# oresat-plusz-end-card.net
KiCad netlist of a schematic drawn in EAGLE
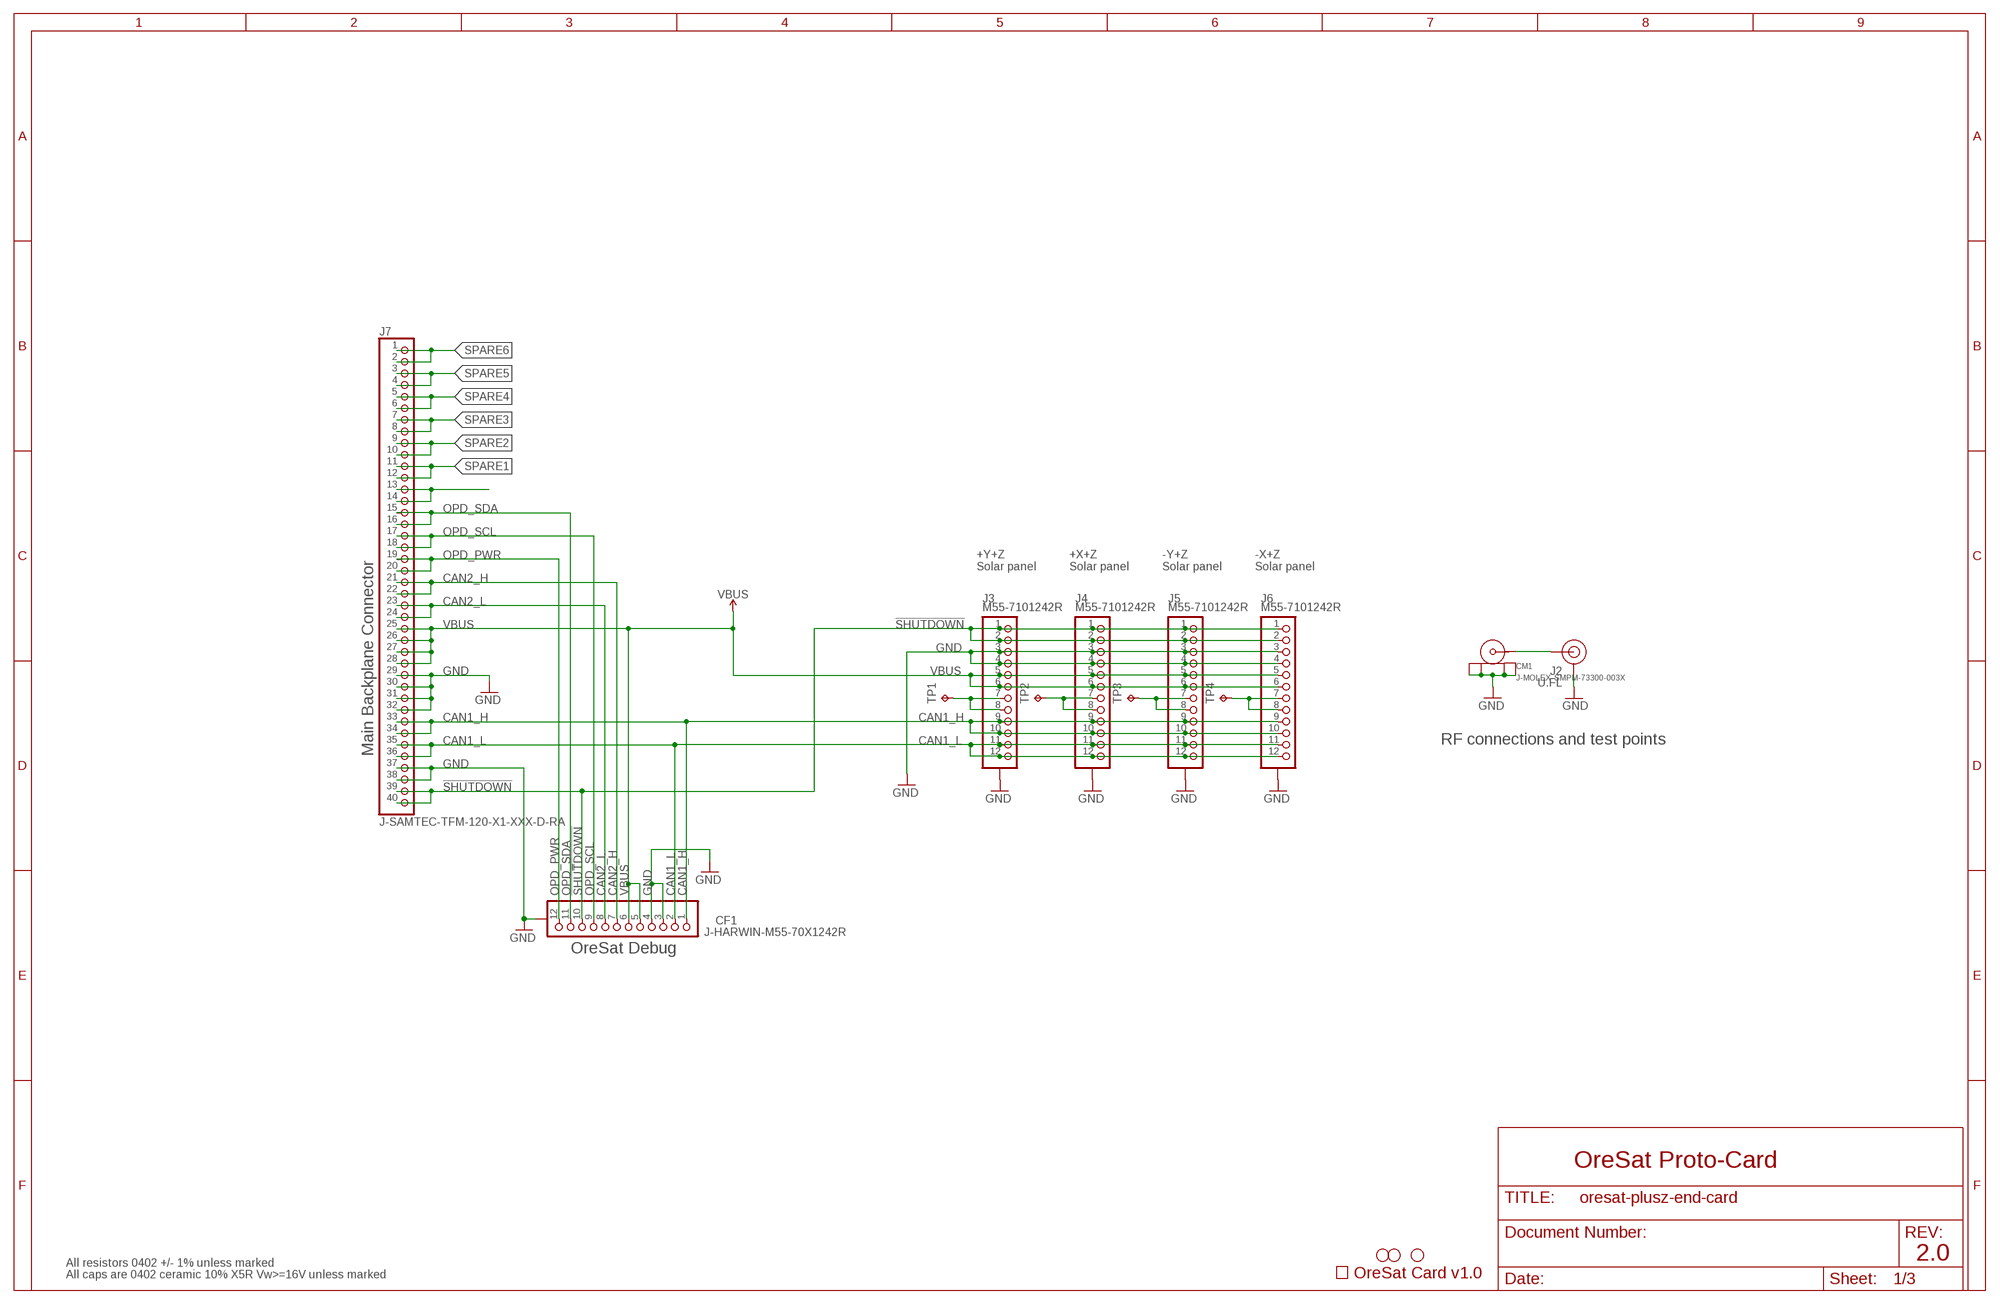
[diagram p0: schematic, sheet 1]
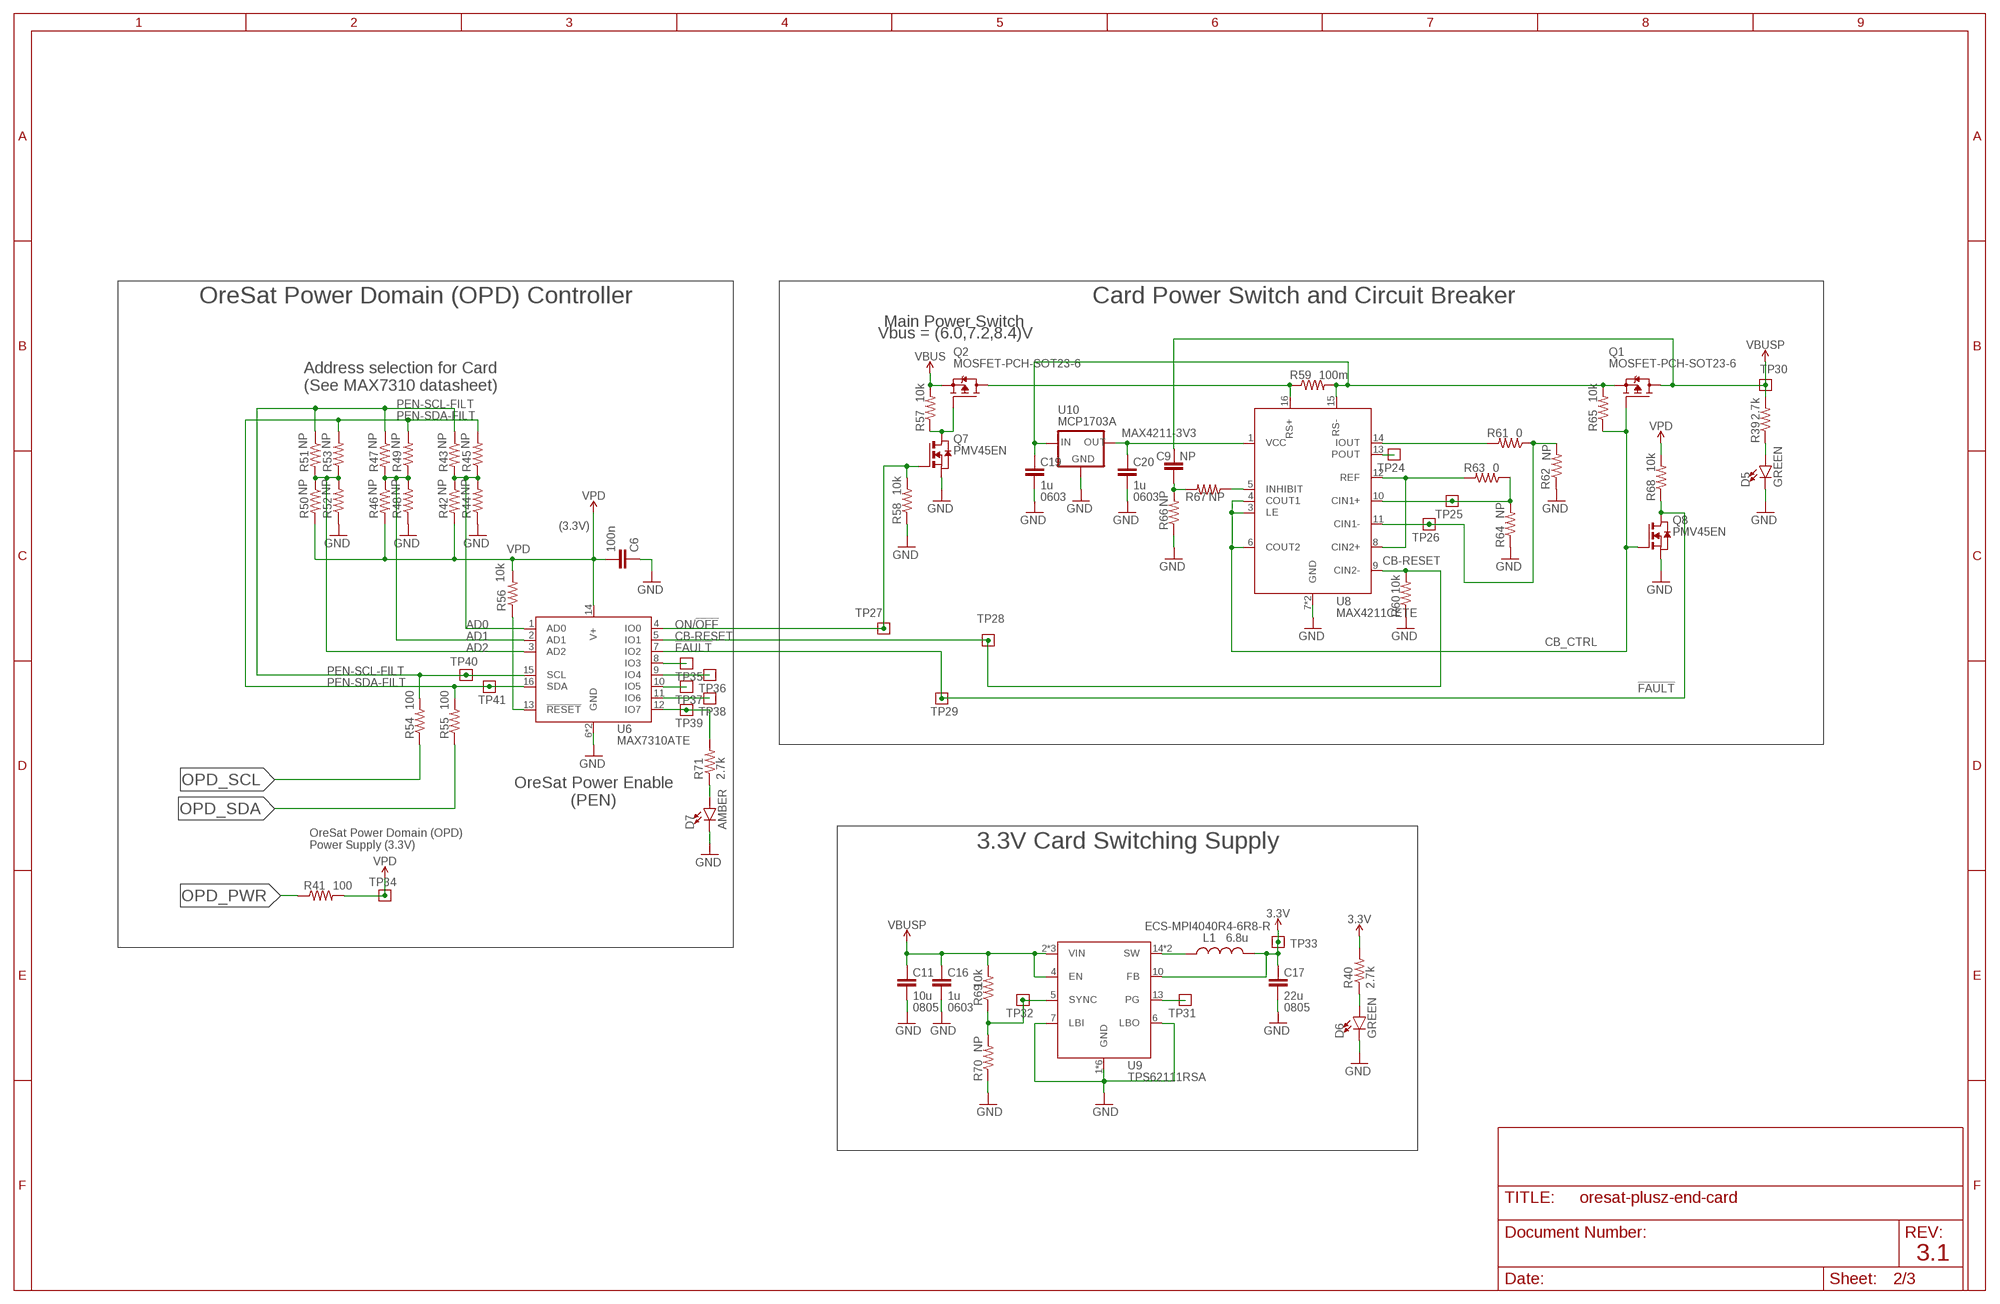
[diagram p1: schematic, sheet 2]
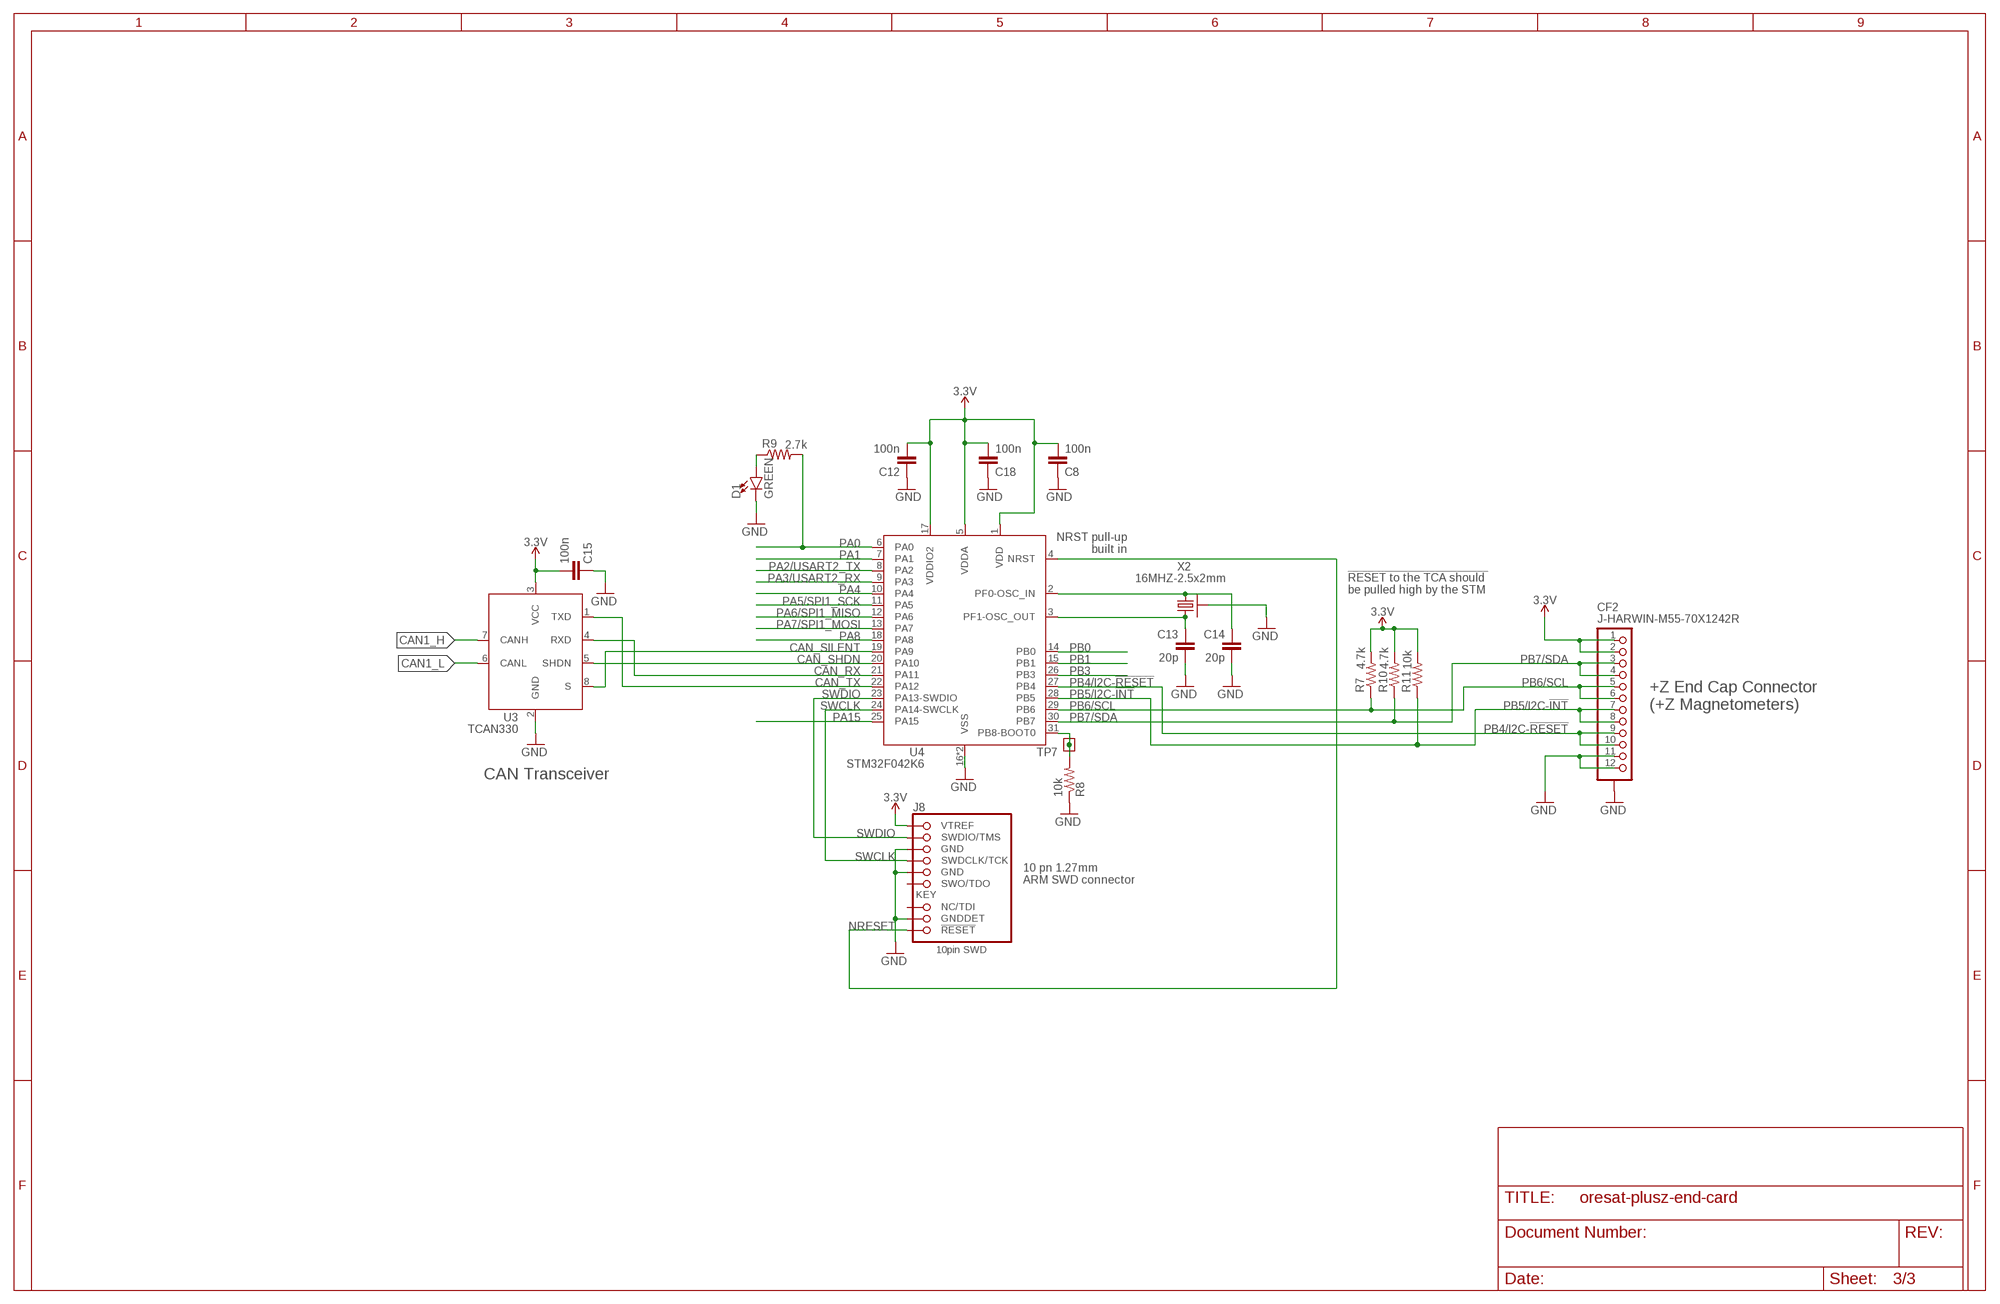
[diagram p2: schematic, sheet 3]

(export (version "E")
  (design (tool "Eeschema 10.0.6"))
  (components
    (comp (ref "CARD")
      (value "ORESAT-CARD-V0.5")
      (footprint "eagle-import:ORESAT-CARD-V1.0")
      (libsource (lib "eagle-import") (part "ORESAT-CARD-V0.5"))
    )
    (comp (ref "CF1")
      (value "J-HARWIN-M55-70X1242R")
      (footprint "eagle-import:HARWIN-M55-70X1242R")
      (libsource (lib "eagle-import") (part "J-HARWIN-M55-70X1242R"))
    )
    (comp (ref "CM1")
      (value "J-MOLEX-SMPM-73300-003X")
      (footprint "eagle-import:J-MOLEX-SMPM-073300-003X")
      (libsource (lib "eagle-import") (part "J-MOLEX-SMPM-73300-003X"))
    )
    (comp (ref "H1")
      (value "STAND-OFFTIGHT")
      (footprint "eagle-import:STAND-OFF-TIGHT")
      (libsource (lib "eagle-import") (part "STAND-OFFTIGHT"))
    )
    (comp (ref "H2")
      (value "STAND-OFFTIGHT")
      (footprint "eagle-import:STAND-OFF-TIGHT")
      (libsource (lib "eagle-import") (part "STAND-OFFTIGHT"))
    )
    (comp (ref "H4")
      (value "STAND-OFFTIGHT")
      (footprint "eagle-import:STAND-OFF-TIGHT")
      (libsource (lib "eagle-import") (part "STAND-OFFTIGHT"))
    )
    (comp (ref "J2")
      (value "U.FL")
      (footprint "eagle-import:U.FL")
      (libsource (lib "eagle-import") (part "U.FL2PIN"))
    )
    (comp (ref "J3")
      (value "M55-7101242R")
      (footprint "eagle-import:M55-7101242R")
      (libsource (lib "eagle-import") (part "M55-7101242R"))
    )
    (comp (ref "J4")
      (value "M55-7101242R")
      (footprint "eagle-import:M55-7101242R")
      (libsource (lib "eagle-import") (part "M55-7101242R"))
    )
    (comp (ref "J5")
      (value "M55-7101242R")
      (footprint "eagle-import:M55-7101242R")
      (libsource (lib "eagle-import") (part "M55-7101242R"))
    )
    (comp (ref "J6")
      (value "M55-7101242R")
      (footprint "eagle-import:M55-7101242R")
      (libsource (lib "eagle-import") (part "M55-7101242R"))
    )
    (comp (ref "J7")
      (value "J-SAMTEC-TFM-120-X1-XXX-D-RA")
      (footprint "eagle-import:J-SAMTEC-TFM-120-X1-XXX-D-RA")
      (libsource (lib "eagle-import") (part "J-SAMTEC-TFM-120-X1-XXX-D-RA"))
    )
    (comp (ref "TP1")
      (value "TPPAD1-13")
      (footprint "eagle-import:P1-13")
      (libsource (lib "eagle-import") (part "TPPAD1-13"))
    )
    (comp (ref "TP2")
      (value "TPPAD1-13")
      (footprint "eagle-import:P1-13")
      (libsource (lib "eagle-import") (part "TPPAD1-13"))
    )
    (comp (ref "TP3")
      (value "TPPAD1-13")
      (footprint "eagle-import:P1-13")
      (libsource (lib "eagle-import") (part "TPPAD1-13"))
    )
    (comp (ref "TP4")
      (value "TPPAD1-13")
      (footprint "eagle-import:P1-13")
      (libsource (lib "eagle-import") (part "TPPAD1-13"))
    )
    (comp (ref "C6")
      (value "100n")
      (footprint "eagle-import:.0402-B-NOSILK")
      (fields (field (name "MFR") "Samsung") (field (name "MPN") "CL05B104KO5NNNC"))
      (libsource (lib "eagle-import") (part "rcl_custom_C-EU0402-B-NOSILK"))
    )
    (comp (ref "C9")
      (value "NP")
      (footprint "eagle-import:.0402-B-NOSILK")
      (fields (field (name "MFR") "Samsung") (field (name "MPN") "CL05B104KO5NNNC"))
      (libsource (lib "eagle-import") (part "rcl_custom_C-EU0402-B-NOSILK"))
    )
    (comp (ref "C11")
      (value "10u")
      (footprint "eagle-import:.0805-B-NOSILK")
      (libsource (lib "eagle-import") (part "C-EU0805-B-NOSILK"))
    )
    (comp (ref "C16")
      (value "1u")
      (footprint "eagle-import:.0603-B-NOSILK")
      (fields (field (name "MFR") "Samsung") (field (name "MPN") "CL05B104KO5NNNC"))
      (libsource (lib "eagle-import") (part "C-EU0603-B-NOSILK"))
    )
    (comp (ref "C17")
      (value "22u")
      (footprint "eagle-import:.0805-B-NOSILK")
      (libsource (lib "eagle-import") (part "C-EU0805-B-NOSILK"))
    )
    (comp (ref "C19")
      (value "1u")
      (footprint "eagle-import:.0603-B-NOSILK")
      (fields (field (name "MFR") "Samsung") (field (name "MPN") "CL05B104KO5NNNC"))
      (libsource (lib "eagle-import") (part "C-EU0603-B-NOSILK"))
    )
    (comp (ref "C20")
      (value "1u")
      (footprint "eagle-import:.0603-B-NOSILK")
      (fields (field (name "MFR") "Samsung") (field (name "MPN") "CL05B104KO5NNNC"))
      (libsource (lib "eagle-import") (part "C-EU0603-B-NOSILK"))
    )
    (comp (ref "D5")
      (value "GREEN")
      (footprint "eagle-import:LED-0603")
      (libsource (lib "eagle-import") (part "LED-GREEN0603"))
    )
    (comp (ref "D6")
      (value "GREEN")
      (footprint "eagle-import:LED-0603")
      (libsource (lib "eagle-import") (part "LED-GREEN0603"))
    )
    (comp (ref "D7")
      (value "AMBER")
      (footprint "eagle-import:LED-0603")
      (libsource (lib "eagle-import") (part "LED-GREEN0603"))
    )
    (comp (ref "L1")
      (value "6.8u")
      (footprint "eagle-import:ECS-MPI4040")
      (fields (field (name "MFR") "ECS") (field (name "MPN") "ECS-MPI4040R4-6R8-R"))
      (libsource (lib "eagle-import") (part "L-ECS-MPI4040"))
    )
    (comp (ref "Q1")
      (value "MOSFET-PCH-SOT23-6")
      (footprint "eagle-import:SOT23-6")
      (fields (field (name "MFR") "Diodes Inc") (field (name "MPN") "DMP3050LVT-7"))
      (libsource (lib "eagle-import") (part "MOSFET-PCH-SOT23-6"))
    )
    (comp (ref "Q2")
      (value "MOSFET-PCH-SOT23-6")
      (footprint "eagle-import:SOT23-6")
      (fields (field (name "MFR") "Diodes Inc") (field (name "MPN") "DMP3050LVT-7"))
      (libsource (lib "eagle-import") (part "MOSFET-PCH-SOT23-6"))
    )
    (comp (ref "Q7")
      (value "PMV45EN")
      (footprint "eagle-import:SOT23")
      (libsource (lib "eagle-import") (part "PMV45EN"))
    )
    (comp (ref "Q8")
      (value "PMV45EN")
      (footprint "eagle-import:SOT23")
      (libsource (lib "eagle-import") (part "PMV45EN"))
    )
    (comp (ref "R39")
      (value "2.7k")
      (footprint "eagle-import:.0402-B-NOSILK")
      (fields (field (name "MFR") "Samsung") (field (name "MPN") "RC1005F6653CS"))
      (libsource (lib "eagle-import") (part "R-US_0402-B-NOSILK"))
    )
    (comp (ref "R40")
      (value "2.7k")
      (footprint "eagle-import:.0402-B-NOSILK")
      (fields (field (name "MFR") "Samsung") (field (name "MPN") "RC1005F6653CS"))
      (libsource (lib "eagle-import") (part "R-US_0402-B-NOSILK"))
    )
    (comp (ref "R41")
      (value "100")
      (footprint "eagle-import:.0402-B-NOSILK")
      (fields (field (name "MFR") "Samsung") (field (name "MPN") "RC1005F6653CS"))
      (libsource (lib "eagle-import") (part "R-US_0402-B-NOSILK"))
    )
    (comp (ref "R42")
      (value "NP")
      (footprint "eagle-import:.0402-B-NOSILK")
      (fields (field (name "MFR") "Samsung") (field (name "MPN") "RC1005F6653CS"))
      (libsource (lib "eagle-import") (part "R-US_0402-B-NOSILK"))
    )
    (comp (ref "R43")
      (value "NP")
      (footprint "eagle-import:.0402-B-NOSILK")
      (fields (field (name "MFR") "Samsung") (field (name "MPN") "RC1005F6653CS"))
      (libsource (lib "eagle-import") (part "R-US_0402-B-NOSILK"))
    )
    (comp (ref "R44")
      (value "NP")
      (footprint "eagle-import:.0402-B-NOSILK")
      (fields (field (name "MFR") "Samsung") (field (name "MPN") "RC1005F6653CS"))
      (libsource (lib "eagle-import") (part "R-US_0402-B-NOSILK"))
    )
    (comp (ref "R45")
      (value "NP")
      (footprint "eagle-import:.0402-B-NOSILK")
      (fields (field (name "MFR") "Samsung") (field (name "MPN") "RC1005F6653CS"))
      (libsource (lib "eagle-import") (part "R-US_0402-B-NOSILK"))
    )
    (comp (ref "R46")
      (value "NP")
      (footprint "eagle-import:.0402-B-NOSILK")
      (fields (field (name "MFR") "Samsung") (field (name "MPN") "RC1005F6653CS"))
      (libsource (lib "eagle-import") (part "R-US_0402-B-NOSILK"))
    )
    (comp (ref "R47")
      (value "NP")
      (footprint "eagle-import:.0402-B-NOSILK")
      (fields (field (name "MFR") "Samsung") (field (name "MPN") "RC1005F6653CS"))
      (libsource (lib "eagle-import") (part "R-US_0402-B-NOSILK"))
    )
    (comp (ref "R48")
      (value "NP")
      (footprint "eagle-import:.0402-B-NOSILK")
      (fields (field (name "MFR") "Samsung") (field (name "MPN") "RC1005F6653CS"))
      (libsource (lib "eagle-import") (part "R-US_0402-B-NOSILK"))
    )
    (comp (ref "R49")
      (value "NP")
      (footprint "eagle-import:.0402-B-NOSILK")
      (fields (field (name "MFR") "Samsung") (field (name "MPN") "RC1005F6653CS"))
      (libsource (lib "eagle-import") (part "R-US_0402-B-NOSILK"))
    )
    (comp (ref "R50")
      (value "NP")
      (footprint "eagle-import:.0402-B-NOSILK")
      (fields (field (name "MFR") "Samsung") (field (name "MPN") "RC1005F6653CS"))
      (libsource (lib "eagle-import") (part "R-US_0402-B-NOSILK"))
    )
    (comp (ref "R51")
      (value "NP")
      (footprint "eagle-import:.0402-B-NOSILK")
      (fields (field (name "MFR") "Samsung") (field (name "MPN") "RC1005F6653CS"))
      (libsource (lib "eagle-import") (part "R-US_0402-B-NOSILK"))
    )
    (comp (ref "R52")
      (value "NP")
      (footprint "eagle-import:.0402-B-NOSILK")
      (fields (field (name "MFR") "Samsung") (field (name "MPN") "RC1005F6653CS"))
      (libsource (lib "eagle-import") (part "R-US_0402-B-NOSILK"))
    )
    (comp (ref "R53")
      (value "NP")
      (footprint "eagle-import:.0402-B-NOSILK")
      (fields (field (name "MFR") "Samsung") (field (name "MPN") "RC1005F6653CS"))
      (libsource (lib "eagle-import") (part "R-US_0402-B-NOSILK"))
    )
    (comp (ref "R54")
      (value "100")
      (footprint "eagle-import:.0402-B-NOSILK")
      (fields (field (name "MFR") "Samsung") (field (name "MPN") "RC1005F6653CS"))
      (libsource (lib "eagle-import") (part "R-US_0402-B-NOSILK"))
    )
    (comp (ref "R55")
      (value "100")
      (footprint "eagle-import:.0402-B-NOSILK")
      (fields (field (name "MFR") "Samsung") (field (name "MPN") "RC1005F6653CS"))
      (libsource (lib "eagle-import") (part "R-US_0402-B-NOSILK"))
    )
    (comp (ref "R56")
      (value "10k")
      (footprint "eagle-import:.0402-B-NOSILK")
      (fields (field (name "MFR") "Samsung") (field (name "MPN") "RC1005F6653CS"))
      (libsource (lib "eagle-import") (part "R-US_0402-B-NOSILK"))
    )
    (comp (ref "R57")
      (value "10k")
      (footprint "eagle-import:.0402-B-NOSILK")
      (fields (field (name "MFR") "Samsung") (field (name "MPN") "RC1005F6653CS"))
      (libsource (lib "eagle-import") (part "R-US_0402-B-NOSILK"))
    )
    (comp (ref "R58")
      (value "10k")
      (footprint "eagle-import:.0402-B-NOSILK")
      (fields (field (name "MFR") "Samsung") (field (name "MPN") "RC1005F6653CS"))
      (libsource (lib "eagle-import") (part "R-US_0402-B-NOSILK"))
    )
    (comp (ref "R59")
      (value "100m")
      (footprint "eagle-import:R1206")
      (libsource (lib "eagle-import") (part "R-US_R1206"))
    )
    (comp (ref "R60")
      (value "10k")
      (footprint "eagle-import:.0402-B-NOSILK")
      (fields (field (name "MFR") "Samsung") (field (name "MPN") "RC1005F6653CS"))
      (libsource (lib "eagle-import") (part "R-US_0402-B-NOSILK"))
    )
    (comp (ref "R61")
      (value "0")
      (footprint "eagle-import:.0402-B-NOSILK")
      (fields (field (name "MFR") "Samsung") (field (name "MPN") "RC1005F6653CS"))
      (libsource (lib "eagle-import") (part "R-US_0402-B-NOSILK"))
    )
    (comp (ref "R62")
      (value "NP")
      (footprint "eagle-import:.0402-B-NOSILK")
      (fields (field (name "MFR") "Samsung") (field (name "MPN") "RC1005F6653CS"))
      (libsource (lib "eagle-import") (part "R-US_0402-B-NOSILK"))
    )
    (comp (ref "R63")
      (value "0")
      (footprint "eagle-import:.0402-B-NOSILK")
      (fields (field (name "MFR") "Samsung") (field (name "MPN") "RC1005F6653CS"))
      (libsource (lib "eagle-import") (part "R-US_0402-B-NOSILK"))
    )
    (comp (ref "R64")
      (value "NP")
      (footprint "eagle-import:.0402-B-NOSILK")
      (fields (field (name "MFR") "Samsung") (field (name "MPN") "RC1005F6653CS"))
      (libsource (lib "eagle-import") (part "R-US_0402-B-NOSILK"))
    )
    (comp (ref "R65")
      (value "10k")
      (footprint "eagle-import:.0402-B-NOSILK")
      (fields (field (name "MFR") "Samsung") (field (name "MPN") "RC1005F6653CS"))
      (libsource (lib "eagle-import") (part "R-US_0402-B-NOSILK"))
    )
    (comp (ref "R66")
      (value "NP")
      (footprint "eagle-import:.0402-B-NOSILK")
      (fields (field (name "MFR") "Samsung") (field (name "MPN") "RC1005F6653CS"))
      (libsource (lib "eagle-import") (part "R-US_0402-B-NOSILK"))
    )
    (comp (ref "R67")
      (value "NP")
      (footprint "eagle-import:.0402-B-NOSILK")
      (fields (field (name "MFR") "Samsung") (field (name "MPN") "RC1005F6653CS"))
      (libsource (lib "eagle-import") (part "R-US_0402-B-NOSILK"))
    )
    (comp (ref "R68")
      (value "10k")
      (footprint "eagle-import:.0402-B-NOSILK")
      (fields (field (name "MFR") "Samsung") (field (name "MPN") "RC1005F6653CS"))
      (libsource (lib "eagle-import") (part "R-US_0402-B-NOSILK"))
    )
    (comp (ref "R69")
      (value "10k")
      (footprint "eagle-import:.0402-B-NOSILK")
      (fields (field (name "MFR") "Samsung") (field (name "MPN") "RC1005F6653CS"))
      (libsource (lib "eagle-import") (part "R-US_0402-B-NOSILK"))
    )
    (comp (ref "R70")
      (value "NP")
      (footprint "eagle-import:.0402-B-NOSILK")
      (fields (field (name "MFR") "Samsung") (field (name "MPN") "RC1005F6653CS"))
      (libsource (lib "eagle-import") (part "R-US_0402-B-NOSILK"))
    )
    (comp (ref "R71")
      (value "2.7k")
      (footprint "eagle-import:.0402-B-NOSILK")
      (fields (field (name "MFR") "Samsung") (field (name "MPN") "RC1005F6653CS"))
      (libsource (lib "eagle-import") (part "R-US_0402-B-NOSILK"))
    )
    (comp (ref "TP24")
      (value "TEST-POINT")
      (footprint "eagle-import:2MM-TEST-POINT")
      (libsource (lib "eagle-import") (part "TEST-POINT"))
    )
    (comp (ref "TP25")
      (value "TEST-POINT")
      (footprint "eagle-import:2MM-TEST-POINT")
      (libsource (lib "eagle-import") (part "TEST-POINT"))
    )
    (comp (ref "TP26")
      (value "TEST-POINT")
      (footprint "eagle-import:2MM-TEST-POINT")
      (libsource (lib "eagle-import") (part "TEST-POINT"))
    )
    (comp (ref "TP27")
      (value "TEST-POINT")
      (footprint "eagle-import:2MM-TEST-POINT")
      (libsource (lib "eagle-import") (part "TEST-POINT"))
    )
    (comp (ref "TP28")
      (value "TEST-POINT")
      (footprint "eagle-import:2MM-TEST-POINT")
      (libsource (lib "eagle-import") (part "TEST-POINT"))
    )
    (comp (ref "TP29")
      (value "TEST-POINT")
      (footprint "eagle-import:2MM-TEST-POINT")
      (libsource (lib "eagle-import") (part "TEST-POINT"))
    )
    (comp (ref "TP30")
      (value "TEST-POINT")
      (footprint "eagle-import:2MM-TEST-POINT")
      (libsource (lib "eagle-import") (part "TEST-POINT"))
    )
    (comp (ref "TP31")
      (value "TEST-POINT")
      (footprint "eagle-import:2MM-TEST-POINT")
      (libsource (lib "eagle-import") (part "TEST-POINT"))
    )
    (comp (ref "TP32")
      (value "TEST-POINT")
      (footprint "eagle-import:2MM-TEST-POINT")
      (libsource (lib "eagle-import") (part "TEST-POINT"))
    )
    (comp (ref "TP33")
      (value "TEST-POINT")
      (footprint "eagle-import:2MM-TEST-POINT")
      (libsource (lib "eagle-import") (part "TEST-POINT"))
    )
    (comp (ref "TP34")
      (value "TEST-POINT")
      (footprint "eagle-import:2MM-TEST-POINT")
      (libsource (lib "eagle-import") (part "TEST-POINT"))
    )
    (comp (ref "TP35")
      (value "TEST-POINT")
      (footprint "eagle-import:2MM-TEST-POINT")
      (libsource (lib "eagle-import") (part "TEST-POINT"))
    )
    (comp (ref "TP36")
      (value "TEST-POINT")
      (footprint "eagle-import:2MM-TEST-POINT")
      (libsource (lib "eagle-import") (part "TEST-POINT"))
    )
    (comp (ref "TP37")
      (value "TEST-POINT")
      (footprint "eagle-import:2MM-TEST-POINT")
      (libsource (lib "eagle-import") (part "TEST-POINT"))
    )
    (comp (ref "TP38")
      (value "TEST-POINT")
      (footprint "eagle-import:2MM-TEST-POINT")
      (libsource (lib "eagle-import") (part "TEST-POINT"))
    )
    (comp (ref "TP39")
      (value "TEST-POINT")
      (footprint "eagle-import:2MM-TEST-POINT")
      (libsource (lib "eagle-import") (part "TEST-POINT"))
    )
    (comp (ref "TP40")
      (value "TEST-POINT")
      (footprint "eagle-import:2MM-TEST-POINT")
      (libsource (lib "eagle-import") (part "TEST-POINT"))
    )
    (comp (ref "TP41")
      (value "TEST-POINT")
      (footprint "eagle-import:2MM-TEST-POINT")
      (libsource (lib "eagle-import") (part "TEST-POINT"))
    )
    (comp (ref "U6")
      (value "MAX7310ATE")
      (footprint "eagle-import:QFN65P400X400X80-17T210")
      (fields (field (name "MFR") "Maxim"))
      (libsource (lib "eagle-import") (part "MAX7310"))
    )
    (comp (ref "U8")
      (value "MAX4211CETE")
      (footprint "eagle-import:QFN65P400X400X80-17T210")
      (fields (field (name "MFR") "Maxim"))
      (libsource (lib "eagle-import") (part "MAX4211"))
    )
    (comp (ref "U9")
      (value "TPS62111RSA")
      (footprint "eagle-import:S-PVQFN-16")
      (fields (field (name "MFR") "TI"))
      (libsource (lib "eagle-import") (part "TPS6211X"))
    )
    (comp (ref "U10")
      (value "MCP1703A")
      (footprint "eagle-import:SOT23")
      (fields (field (name "MFR") "Microchip") (field (name "MPN") "MCP1703AT-3302E/CB"))
      (libsource (lib "eagle-import") (part "XC63FPM"))
    )
    (comp (ref "C8")
      (value "100n")
      (footprint "eagle-import:.0402-B-NOSILK")
      (fields (field (name "MFR") "Samsung") (field (name "MPN") "CL05B104KO5NNNC"))
      (libsource (lib "eagle-import") (part "rcl_custom_C-EU0402-B-NOSILK"))
    )
    (comp (ref "C12")
      (value "100n")
      (footprint "eagle-import:.0402-B-NOSILK")
      (fields (field (name "MFR") "Samsung") (field (name "MPN") "CL05B104KO5NNNC"))
      (libsource (lib "eagle-import") (part "rcl_custom_C-EU0402-B-NOSILK"))
    )
    (comp (ref "C13")
      (value "20p")
      (footprint "eagle-import:.0402-B-NOSILK")
      (fields (field (name "MFR") "Samsung") (field (name "MPN") "CL05C200JB51PNC"))
      (libsource (lib "eagle-import") (part "rcl_custom_C-EU0402-B-NOSILK"))
    )
    (comp (ref "C14")
      (value "20p")
      (footprint "eagle-import:.0402-B-NOSILK")
      (fields (field (name "MFR") "Samsung") (field (name "MPN") "CL05C200JB51PNC"))
      (libsource (lib "eagle-import") (part "rcl_custom_C-EU0402-B-NOSILK"))
    )
    (comp (ref "C15")
      (value "100n")
      (footprint "eagle-import:.0402-B-NOSILK")
      (fields (field (name "MFR") "Samsung") (field (name "MPN") "CL05B104KO5NNNC"))
      (libsource (lib "eagle-import") (part "rcl_custom_C-EU0402-B-NOSILK"))
    )
    (comp (ref "C18")
      (value "100n")
      (footprint "eagle-import:.0402-B-NOSILK")
      (fields (field (name "MFR") "Samsung") (field (name "MPN") "CL05B104KO5NNNC"))
      (libsource (lib "eagle-import") (part "rcl_custom_C-EU0402-B-NOSILK"))
    )
    (comp (ref "CF2")
      (value "J-HARWIN-M55-70X1242R")
      (footprint "eagle-import:HARWIN-M55-70X1242R")
      (libsource (lib "eagle-import") (part "J-HARWIN-M55-70X1242R"))
    )
    (comp (ref "D1")
      (value "GREEN")
      (footprint "eagle-import:LED-0603")
      (libsource (lib "eagle-import") (part "LED-GREEN0603"))
    )
    (comp (ref "J8")
      (value "FTSH-105-XX-X-DV-K")
      (footprint "eagle-import:CON10_2X5_DUK_FTSH")
      (fields (field (name "MFR") "CNC Tech") (field (name "MPN") "3220-10-0100-00"))
      (libsource (lib "eagle-import") (part "FTSH-105-XX-X-DV-K"))
    )
    (comp (ref "R7")
      (value "4.7k")
      (footprint "eagle-import:.0402-B-NOSILK")
      (fields (field (name "MFR") "Samsung") (field (name "MPN") "RC1005F6653CS"))
      (libsource (lib "eagle-import") (part "R-US_0402-B-NOSILK"))
    )
    (comp (ref "R8")
      (value "10k")
      (footprint "eagle-import:.0402-B-NOSILK")
      (fields (field (name "MFR") "Samsung") (field (name "MPN") "RC1005F6653CS"))
      (libsource (lib "eagle-import") (part "R-US_0402-B-NOSILK"))
    )
    (comp (ref "R9")
      (value "2.7k")
      (footprint "eagle-import:.0402-B-NOSILK")
      (fields (field (name "MFR") "Samsung") (field (name "MPN") "RC1005F6653CS"))
      (libsource (lib "eagle-import") (part "R-US_0402-B-NOSILK"))
    )
    (comp (ref "R10")
      (value "4.7k")
      (footprint "eagle-import:.0402-B-NOSILK")
      (fields (field (name "MFR") "Samsung") (field (name "MPN") "RC1005F6653CS"))
      (libsource (lib "eagle-import") (part "R-US_0402-B-NOSILK"))
    )
    (comp (ref "R11")
      (value "10k")
      (footprint "eagle-import:.0402-B-NOSILK")
      (fields (field (name "MFR") "Samsung") (field (name "MPN") "RC1005F6653CS"))
      (libsource (lib "eagle-import") (part "R-US_0402-B-NOSILK"))
    )
    (comp (ref "TP7")
      (value "TEST-POINT")
      (footprint "eagle-import:2MM-TEST-POINT")
      (libsource (lib "eagle-import") (part "TEST-POINT"))
    )
    (comp (ref "U3")
      (value "TCAN330")
      (footprint "eagle-import:SOT23-8_TI-DCN")
      (fields (field (name "MFR") "Texas Instruments") (field (name "MPN") "TCAN330GDCNT"))
      (libsource (lib "eagle-import") (part "TCAN330"))
    )
    (comp (ref "U4")
      (value "STM32F042K6")
      (footprint "eagle-import:QFP32-7X7")
      (fields (field (name "MFR") "STMicroelectronics") (field (name "MPN") "STM32F042K6T7"))
      (libsource (lib "eagle-import") (part "STM32F042K6"))
    )
    (comp (ref "X2")
      (value "16MHZ-2.5x2mm")
      (footprint "eagle-import:CRYSTAL_2.5X2")
      (fields (field (name "MFR") "ECS Inc.") (field (name "MPN") "ECS-160-10-36Q-ES-TR"))
      (libsource (lib "eagle-import") (part "CRYSTAL-WITH-GND"))
    )
  )
  (nets
    (net (code "1") (name "3.3V") (class "Default")
      (node (ref "C12") (pin "2") (pinfunction "2_2") (pintype "passive"))
      (node (ref "C15") (pin "2") (pinfunction "2_2") (pintype "passive"))
      (node (ref "C17") (pin "1") (pinfunction "1_1") (pintype "passive"))
      (node (ref "C18") (pin "2") (pinfunction "2_2") (pintype "passive"))
      (node (ref "C8") (pin "2") (pinfunction "2_2") (pintype "passive"))
      (node (ref "CF2") (pin "1") (pinfunction "1_1") (pintype "passive"))
      (node (ref "CF2") (pin "2") (pinfunction "2_2") (pintype "passive"))
      (node (ref "J8") (pin "1") (pinfunction "VTREF_1") (pintype "passive"))
      (node (ref "L1") (pin "2") (pinfunction "2_2") (pintype "passive"))
      (node (ref "R10") (pin "2") (pinfunction "2_2") (pintype "passive"))
      (node (ref "R11") (pin "2") (pinfunction "2_2") (pintype "passive"))
      (node (ref "R40") (pin "2") (pinfunction "2_2") (pintype "passive"))
      (node (ref "R7") (pin "2") (pinfunction "2_2") (pintype "passive"))
      (node (ref "TP33") (pin "1") (pinfunction "1_1") (pintype "passive"))
      (node (ref "U3") (pin "3") (pinfunction "VCC_3") (pintype "power_in"))
      (node (ref "U4") (pin "1") (pinfunction "VDD_1") (pintype "power_in"))
      (node (ref "U4") (pin "17") (pinfunction "VDDIO2_17") (pintype "power_in"))
      (node (ref "U4") (pin "5") (pinfunction "VDDA_5") (pintype "power_in"))
      (node (ref "U9") (pin "10") (pinfunction "FB_10") (pintype "input"))
    )
    (net (code "2") (name "AD0") (class "Default")
      (node (ref "R42") (pin "1") (pinfunction "1_1") (pintype "passive"))
      (node (ref "R43") (pin "2") (pinfunction "2_2") (pintype "passive"))
      (node (ref "R44") (pin "2") (pinfunction "2_2") (pintype "passive"))
      (node (ref "R45") (pin "1") (pinfunction "1_1") (pintype "passive"))
      (node (ref "U6") (pin "1") (pinfunction "AD0_1") (pintype "input"))
    )
    (net (code "3") (name "AD1") (class "Default")
      (node (ref "R46") (pin "1") (pinfunction "1_1") (pintype "passive"))
      (node (ref "R47") (pin "2") (pinfunction "2_2") (pintype "passive"))
      (node (ref "R48") (pin "2") (pinfunction "2_2") (pintype "passive"))
      (node (ref "R49") (pin "1") (pinfunction "1_1") (pintype "passive"))
      (node (ref "U6") (pin "2") (pinfunction "AD1_2") (pintype "input"))
    )
    (net (code "4") (name "AD2") (class "Default")
      (node (ref "R50") (pin "1") (pinfunction "1_1") (pintype "passive"))
      (node (ref "R51") (pin "2") (pinfunction "2_2") (pintype "passive"))
      (node (ref "R52") (pin "2") (pinfunction "2_2") (pintype "passive"))
      (node (ref "R53") (pin "1") (pinfunction "1_1") (pintype "passive"))
      (node (ref "U6") (pin "3") (pinfunction "AD2_3") (pintype "input"))
    )
    (net (code "5") (name "CAN1_H") (class "Default")
      (node (ref "CF1") (pin "1") (pinfunction "1_1") (pintype "passive"))
      (node (ref "J3") (pin "10") (pinfunction "10_10") (pintype "passive"))
      (node (ref "J3") (pin "9") (pinfunction "9_9") (pintype "passive"))
      (node (ref "J4") (pin "10") (pinfunction "10_10") (pintype "passive"))
      (node (ref "J4") (pin "9") (pinfunction "9_9") (pintype "passive"))
      (node (ref "J5") (pin "10") (pinfunction "10_10") (pintype "passive"))
      (node (ref "J5") (pin "9") (pinfunction "9_9") (pintype "passive"))
      (node (ref "J6") (pin "10") (pinfunction "10_10") (pintype "passive"))
      (node (ref "J6") (pin "9") (pinfunction "9_9") (pintype "passive"))
      (node (ref "J7") (pin "33") (pinfunction "33_33") (pintype "passive"))
      (node (ref "J7") (pin "34") (pinfunction "34_34") (pintype "passive"))
      (node (ref "U3") (pin "7") (pinfunction "CANH_7") (pintype "bidirectional"))
    )
    (net (code "6") (name "CAN1_L") (class "Default")
      (node (ref "CF1") (pin "2") (pinfunction "2_2") (pintype "passive"))
      (node (ref "J3") (pin "11") (pinfunction "11_11") (pintype "passive"))
      (node (ref "J3") (pin "12") (pinfunction "12_12") (pintype "passive"))
      (node (ref "J4") (pin "11") (pinfunction "11_11") (pintype "passive"))
      (node (ref "J4") (pin "12") (pinfunction "12_12") (pintype "passive"))
      (node (ref "J5") (pin "11") (pinfunction "11_11") (pintype "passive"))
      (node (ref "J5") (pin "12") (pinfunction "12_12") (pintype "passive"))
      (node (ref "J6") (pin "11") (pinfunction "11_11") (pintype "passive"))
      (node (ref "J6") (pin "12") (pinfunction "12_12") (pintype "passive"))
      (node (ref "J7") (pin "35") (pinfunction "35_35") (pintype "passive"))
      (node (ref "J7") (pin "36") (pinfunction "36_36") (pintype "passive"))
      (node (ref "U3") (pin "6") (pinfunction "CANL_6") (pintype "bidirectional"))
    )
    (net (code "7") (name "CAN2_H") (class "Default")
      (node (ref "CF1") (pin "7") (pinfunction "7_7") (pintype "passive"))
      (node (ref "J7") (pin "21") (pinfunction "21_21") (pintype "passive"))
      (node (ref "J7") (pin "22") (pinfunction "22_22") (pintype "passive"))
    )
    (net (code "8") (name "CAN2_L") (class "Default")
      (node (ref "CF1") (pin "8") (pinfunction "8_8") (pintype "passive"))
      (node (ref "J7") (pin "23") (pinfunction "23_23") (pintype "passive"))
      (node (ref "J7") (pin "24") (pinfunction "24_24") (pintype "passive"))
    )
    (net (code "9") (name "CAN_RX") (class "Default")
      (node (ref "U3") (pin "4") (pinfunction "RXD_4") (pintype "output"))
      (node (ref "U4") (pin "21") (pinfunction "PA11_21") (pintype "bidirectional"))
    )
    (net (code "10") (name "CAN_SHDN") (class "Default")
      (node (ref "U3") (pin "5") (pinfunction "SHDN_5") (pintype "input"))
      (node (ref "U4") (pin "20") (pinfunction "PA10_20") (pintype "bidirectional"))
    )
    (net (code "11") (name "CAN_SILENT") (class "Default")
      (node (ref "U3") (pin "8") (pinfunction "S_8") (pintype "input"))
      (node (ref "U4") (pin "19") (pinfunction "PA9_19") (pintype "bidirectional"))
    )
    (net (code "12") (name "CAN_TX") (class "Default")
      (node (ref "U3") (pin "1") (pinfunction "TXD_1") (pintype "input"))
      (node (ref "U4") (pin "22") (pinfunction "PA12_22") (pintype "bidirectional"))
    )
    (net (code "13") (name "CB-RESET") (class "Default")
      (node (ref "R60") (pin "2") (pinfunction "2_2") (pintype "passive"))
      (node (ref "TP28") (pin "1") (pinfunction "1_1") (pintype "passive"))
      (node (ref "U6") (pin "5") (pinfunction "IO1_5") (pintype "bidirectional"))
      (node (ref "U8") (pin "9") (pinfunction "CIN2-_9") (pintype "input"))
    )
    (net (code "14") (name "CB_CTRL") (class "Default")
      (node (ref "Q1") (pin "3") (pinfunction "G_3") (pintype "passive"))
      (node (ref "Q8") (pin "1") (pinfunction "G_1") (pintype "passive"))
      (node (ref "R65") (pin "1") (pinfunction "1_1") (pintype "passive"))
      (node (ref "U8") (pin "3") (pinfunction "LE_3") (pintype "input"))
      (node (ref "U8") (pin "4") (pinfunction "COUT1_4") (pintype "open_collector"))
      (node (ref "U8") (pin "6") (pinfunction "COUT2_6") (pintype "open_collector"))
    )
    (net (code "15") (name "GND") (class "Default")
      (node (ref "C11") (pin "2") (pinfunction "2_2") (pintype "passive"))
      (node (ref "C12") (pin "1") (pinfunction "1_1") (pintype "passive"))
      (node (ref "C13") (pin "2") (pinfunction "2_2") (pintype "passive"))
      (node (ref "C14") (pin "2") (pinfunction "2_2") (pintype "passive"))
      (node (ref "C15") (pin "1") (pinfunction "1_1") (pintype "passive"))
      (node (ref "C16") (pin "2") (pinfunction "2_2") (pintype "passive"))
      (node (ref "C17") (pin "2") (pinfunction "2_2") (pintype "passive"))
      (node (ref "C18") (pin "1") (pinfunction "1_1") (pintype "passive"))
      (node (ref "C19") (pin "2") (pinfunction "2_2") (pintype "passive"))
      (node (ref "C20") (pin "2") (pinfunction "2_2") (pintype "passive"))
      (node (ref "C6") (pin "1") (pinfunction "1_1") (pintype "passive"))
      (node (ref "C8") (pin "1") (pinfunction "1_1") (pintype "passive"))
      (node (ref "CF1") (pin "3") (pinfunction "3_3") (pintype "passive"))
      (node (ref "CF1") (pin "4") (pinfunction "4_4") (pintype "passive"))
      (node (ref "CF1") (pin "P$1") (pinfunction "SHIELDS_P$1") (pintype "passive"))
      (node (ref "CF1") (pin "P$2") (pinfunction "SHIELDS_P$2") (pintype "passive"))
      (node (ref "CF1") (pin "P$3") (pinfunction "SHIELDS_P$3") (pintype "passive"))
      (node (ref "CF1") (pin "P$4") (pinfunction "SHIELDS_P$4") (pintype "passive"))
      (node (ref "CF2") (pin "11") (pinfunction "11_11") (pintype "passive"))
      (node (ref "CF2") (pin "12") (pinfunction "12_12") (pintype "passive"))
      (node (ref "CF2") (pin "P$1") (pinfunction "SHIELDS_P$1") (pintype "passive"))
      (node (ref "CF2") (pin "P$2") (pinfunction "SHIELDS_P$2") (pintype "passive"))
      (node (ref "CF2") (pin "P$3") (pinfunction "SHIELDS_P$3") (pintype "passive"))
      (node (ref "CF2") (pin "P$4") (pinfunction "SHIELDS_P$4") (pintype "passive"))
      (node (ref "CM1") (pin "P$1") (pinfunction "SHIELD3_P$1") (pintype "passive"))
      (node (ref "CM1") (pin "P$2") (pinfunction "SHIELD2_P$2") (pintype "passive"))
      (node (ref "CM1") (pin "P$3") (pinfunction "SHIELD1_P$3") (pintype "passive"))
      (node (ref "CM1") (pin "P$4") (pinfunction "SHIELD_P$4") (pintype "passive"))
      (node (ref "D1") (pin "C") (pinfunction "C_C") (pintype "passive"))
      (node (ref "D5") (pin "C") (pinfunction "C_C") (pintype "passive"))
      (node (ref "D6") (pin "C") (pinfunction "C_C") (pintype "passive"))
      (node (ref "D7") (pin "C") (pinfunction "C_C") (pintype "passive"))
      (node (ref "J2") (pin "1") (pinfunction "GND_1") (pintype "bidirectional"))
      (node (ref "J2") (pin "2") (pinfunction "GND_2") (pintype "bidirectional"))
      (node (ref "J3") (pin "3") (pinfunction "3_3") (pintype "passive"))
      (node (ref "J3") (pin "4") (pinfunction "4_4") (pintype "passive"))
      (node (ref "J3") (pin "P$1") (pinfunction "SHIELD_P$1") (pintype "passive"))
      (node (ref "J3") (pin "P$2") (pinfunction "SHIELD_P$2") (pintype "passive"))
      (node (ref "J3") (pin "P$3") (pinfunction "SHIELD_P$3") (pintype "passive"))
      (node (ref "J3") (pin "P$4") (pinfunction "SHIELD_P$4") (pintype "passive"))
      (node (ref "J4") (pin "3") (pinfunction "3_3") (pintype "passive"))
      (node (ref "J4") (pin "4") (pinfunction "4_4") (pintype "passive"))
      (node (ref "J4") (pin "P$1") (pinfunction "SHIELD_P$1") (pintype "passive"))
      (node (ref "J4") (pin "P$2") (pinfunction "SHIELD_P$2") (pintype "passive"))
      (node (ref "J4") (pin "P$3") (pinfunction "SHIELD_P$3") (pintype "passive"))
      (node (ref "J4") (pin "P$4") (pinfunction "SHIELD_P$4") (pintype "passive"))
      (node (ref "J5") (pin "3") (pinfunction "3_3") (pintype "passive"))
      (node (ref "J5") (pin "4") (pinfunction "4_4") (pintype "passive"))
      (node (ref "J5") (pin "P$1") (pinfunction "SHIELD_P$1") (pintype "passive"))
      (node (ref "J5") (pin "P$2") (pinfunction "SHIELD_P$2") (pintype "passive"))
      (node (ref "J5") (pin "P$3") (pinfunction "SHIELD_P$3") (pintype "passive"))
      (node (ref "J5") (pin "P$4") (pinfunction "SHIELD_P$4") (pintype "passive"))
      (node (ref "J6") (pin "3") (pinfunction "3_3") (pintype "passive"))
      (node (ref "J6") (pin "4") (pinfunction "4_4") (pintype "passive"))
      (node (ref "J6") (pin "P$1") (pinfunction "SHIELD_P$1") (pintype "passive"))
      (node (ref "J6") (pin "P$2") (pinfunction "SHIELD_P$2") (pintype "passive"))
      (node (ref "J6") (pin "P$3") (pinfunction "SHIELD_P$3") (pintype "passive"))
      (node (ref "J6") (pin "P$4") (pinfunction "SHIELD_P$4") (pintype "passive"))
      (node (ref "J7") (pin "29") (pinfunction "29_29") (pintype "passive"))
      (node (ref "J7") (pin "30") (pinfunction "30_30") (pintype "passive"))
      (node (ref "J7") (pin "31") (pinfunction "31_31") (pintype "passive"))
      (node (ref "J7") (pin "32") (pinfunction "32_32") (pintype "passive"))
      (node (ref "J7") (pin "37") (pinfunction "37_37") (pintype "passive"))
      (node (ref "J7") (pin "38") (pinfunction "38_38") (pintype "passive"))
      (node (ref "J8") (pin "3") (pinfunction "GND_3") (pintype "passive"))
      (node (ref "J8") (pin "5") (pinfunction "GND_5") (pintype "passive"))
      (node (ref "J8") (pin "9") (pinfunction "GNDDET_9") (pintype "passive"))
      (node (ref "Q7") (pin "2") (pinfunction "S_2") (pintype "passive"))
      (node (ref "Q8") (pin "2") (pinfunction "S_2") (pintype "passive"))
      (node (ref "R44") (pin "1") (pinfunction "1_1") (pintype "passive"))
      (node (ref "R48") (pin "1") (pinfunction "1_1") (pintype "passive"))
      (node (ref "R52") (pin "1") (pinfunction "1_1") (pintype "passive"))
      (node (ref "R58") (pin "1") (pinfunction "1_1") (pintype "passive"))
      (node (ref "R60") (pin "1") (pinfunction "1_1") (pintype "passive"))
      (node (ref "R62") (pin "1") (pinfunction "1_1") (pintype "passive"))
      (node (ref "R64") (pin "1") (pinfunction "1_1") (pintype "passive"))
      (node (ref "R66") (pin "1") (pinfunction "1_1") (pintype "passive"))
      (node (ref "R70") (pin "1") (pinfunction "1_1") (pintype "passive"))
      (node (ref "R8") (pin "1") (pinfunction "1_1") (pintype "passive"))
      (node (ref "U10") (pin "1") (pinfunction "GND_1") (pintype "input"))
      (node (ref "U3") (pin "2") (pinfunction "GND_2") (pintype "power_in"))
      (node (ref "U4") (pin "16") (pinfunction "VSS_16") (pintype "power_in"))
      (node (ref "U4") (pin "32") (pinfunction "VSS_32") (pintype "power_in"))
      (node (ref "U6") (pin "6") (pinfunction "GND_6") (pintype "power_in"))
      (node (ref "U6") (pin "EPAD") (pinfunction "GND_EPAD") (pintype "power_in"))
      (node (ref "U8") (pin "7") (pinfunction "GND_7") (pintype "power_in"))
      (node (ref "U8") (pin "EPAD") (pinfunction "GND_EPAD") (pintype "power_in"))
      (node (ref "U9") (pin "1") (pinfunction "GND_1") (pintype "power_in"))
      (node (ref "U9") (pin "11") (pinfunction "GND_11") (pintype "power_in"))
      (node (ref "U9") (pin "12") (pinfunction "GND_12") (pintype "power_in"))
      (node (ref "U9") (pin "16") (pinfunction "GND_16") (pintype "power_in"))
      (node (ref "U9") (pin "6") (pinfunction "LBO_6") (pintype "open_collector"))
      (node (ref "U9") (pin "7") (pinfunction "LBI_7") (pintype "input"))
      (node (ref "U9") (pin "9") (pinfunction "GND_9") (pintype "power_in"))
      (node (ref "U9") (pin "PAD") (pinfunction "GND_PAD") (pintype "power_in"))
      (node (ref "X2") (pin "2") (pinfunction "SHIELD_2") (pintype "power_in"))
      (node (ref "X2") (pin "4") (pinfunction "SHIELD_4") (pintype "power_in"))
    )
    (net (code "16") (name "MAX4211-3V3") (class "Default")
      (node (ref "C20") (pin "1") (pinfunction "1_1") (pintype "passive"))
      (node (ref "U10") (pin "2") (pinfunction "OUT_2") (pintype "passive"))
      (node (ref "U8") (pin "1") (pinfunction "VCC_1") (pintype "power_in"))
    )
    (net (code "17") (name "NRESET") (class "Default")
      (node (ref "J8") (pin "10") (pinfunction "~{RESET}_10") (pintype "passive"))
      (node (ref "U4") (pin "4") (pinfunction "NRST_4") (pintype "bidirectional"))
    )
    (net (code "18") (name "Net-(C9-Pad1)") (class "Default")
      (node (ref "C9") (pin "1") (pinfunction "1_1") (pintype "passive"))
      (node (ref "R66") (pin "2") (pinfunction "2_2") (pintype "passive"))
      (node (ref "R67") (pin "2") (pinfunction "2_2") (pintype "passive"))
    )
    (net (code "19") (name "Net-(CM1-CENTER)") (class "Default")
      (node (ref "CM1") (pin "RF") (pinfunction "CENTER_RF") (pintype "passive"))
      (node (ref "J2") (pin "FEED") (pinfunction "SIGNAL_FEED") (pintype "bidirectional"))
    )
    (net (code "20") (name "Net-(D1-PadA)") (class "Default")
      (node (ref "D1") (pin "A") (pinfunction "A_A") (pintype "passive"))
      (node (ref "R9") (pin "1") (pinfunction "1_1") (pintype "passive"))
    )
    (net (code "21") (name "Net-(D5-PadA)") (class "Default")
      (node (ref "D5") (pin "A") (pinfunction "A_A") (pintype "passive"))
      (node (ref "R39") (pin "1") (pinfunction "1_1") (pintype "passive"))
    )
    (net (code "22") (name "Net-(D6-PadA)") (class "Default")
      (node (ref "D6") (pin "A") (pinfunction "A_A") (pintype "passive"))
      (node (ref "R40") (pin "1") (pinfunction "1_1") (pintype "passive"))
    )
    (net (code "23") (name "Net-(D7-PadA)") (class "Default")
      (node (ref "D7") (pin "A") (pinfunction "A_A") (pintype "passive"))
      (node (ref "R71") (pin "1") (pinfunction "1_1") (pintype "passive"))
    )
    (net (code "24") (name "Net-(J3-Pad7)") (class "Default")
      (node (ref "J3") (pin "7") (pinfunction "7_7") (pintype "passive"))
      (node (ref "J3") (pin "8") (pinfunction "8_8") (pintype "passive"))
      (node (ref "TP1") (pin "TP") (pinfunction "TP_TP") (pintype "input"))
    )
    (net (code "25") (name "Net-(J4-Pad7)") (class "Default")
      (node (ref "J4") (pin "7") (pinfunction "7_7") (pintype "passive"))
      (node (ref "J4") (pin "8") (pinfunction "8_8") (pintype "passive"))
      (node (ref "TP2") (pin "TP") (pinfunction "TP_TP") (pintype "input"))
    )
    (net (code "26") (name "Net-(J5-Pad7)") (class "Default")
      (node (ref "J5") (pin "7") (pinfunction "7_7") (pintype "passive"))
      (node (ref "J5") (pin "8") (pinfunction "8_8") (pintype "passive"))
      (node (ref "TP3") (pin "TP") (pinfunction "TP_TP") (pintype "input"))
    )
    (net (code "27") (name "Net-(J6-Pad7)") (class "Default")
      (node (ref "J6") (pin "7") (pinfunction "7_7") (pintype "passive"))
      (node (ref "J6") (pin "8") (pinfunction "8_8") (pintype "passive"))
      (node (ref "TP4") (pin "TP") (pinfunction "TP_TP") (pintype "input"))
    )
    (net (code "28") (name "Net-(J7-Pad13)") (class "Default")
      (node (ref "J7") (pin "13") (pinfunction "13_13") (pintype "passive"))
      (node (ref "J7") (pin "14") (pinfunction "14_14") (pintype "passive"))
    )
    (net (code "29") (name "Net-(L1-Pad1)") (class "Default")
      (node (ref "L1") (pin "1") (pinfunction "1_1") (pintype "passive"))
      (node (ref "U9") (pin "14") (pinfunction "SW_14") (pintype "output"))
      (node (ref "U9") (pin "15") (pinfunction "SW_15") (pintype "output"))
    )
    (net (code "30") (name "Net-(Q1-S)") (class "Default")
      (node (ref "C19") (pin "1") (pinfunction "1_1") (pintype "passive"))
      (node (ref "Q1") (pin "4") (pinfunction "S_4") (pintype "passive"))
      (node (ref "R59") (pin "2") (pinfunction "2_2") (pintype "passive"))
      (node (ref "R65") (pin "2") (pinfunction "2_2") (pintype "passive"))
      (node (ref "U10") (pin "3") (pinfunction "IN_3") (pintype "input"))
      (node (ref "U8") (pin "15") (pinfunction "RS-_15") (pintype "passive"))
    )
    (net (code "31") (name "Net-(Q2-G)") (class "Default")
      (node (ref "Q2") (pin "3") (pinfunction "G_3") (pintype "passive"))
      (node (ref "Q7") (pin "3") (pinfunction "D_3") (pintype "passive"))
      (node (ref "R57") (pin "1") (pinfunction "1_1") (pintype "passive"))
    )
    (net (code "32") (name "Net-(U4-PB8-BOOT0)") (class "Default")
      (node (ref "R8") (pin "2") (pinfunction "2_2") (pintype "passive"))
      (node (ref "TP7") (pin "1") (pinfunction "1_1") (pintype "passive"))
      (node (ref "U4") (pin "31") (pinfunction "PB8-BOOT0_31") (pintype "bidirectional"))
    )
    (net (code "33") (name "Net-(U4-PF0-OSC_IN)") (class "Default")
      (node (ref "C14") (pin "1") (pinfunction "1_1") (pintype "passive"))
      (node (ref "U4") (pin "2") (pinfunction "PF0-OSC_IN_2") (pintype "bidirectional"))
      (node (ref "X2") (pin "1") (pinfunction "1_1") (pintype "passive"))
    )
    (net (code "34") (name "Net-(U4-PF1-OSC_OUT)") (class "Default")
      (node (ref "C13") (pin "1") (pinfunction "1_1") (pintype "passive"))
      (node (ref "U4") (pin "3") (pinfunction "PF1-OSC_OUT_3") (pintype "bidirectional"))
      (node (ref "X2") (pin "3") (pinfunction "2_3") (pintype "passive"))
    )
    (net (code "35") (name "Net-(U6-IO3)") (class "Default")
      (node (ref "TP35") (pin "1") (pinfunction "1_1") (pintype "passive"))
      (node (ref "U6") (pin "8") (pinfunction "IO3_8") (pintype "bidirectional"))
    )
    (net (code "36") (name "Net-(U6-IO4)") (class "Default")
      (node (ref "TP36") (pin "1") (pinfunction "1_1") (pintype "passive"))
      (node (ref "U6") (pin "9") (pinfunction "IO4_9") (pintype "bidirectional"))
    )
    (net (code "37") (name "Net-(U6-IO5)") (class "Default")
      (node (ref "TP37") (pin "1") (pinfunction "1_1") (pintype "passive"))
      (node (ref "U6") (pin "10") (pinfunction "IO5_10") (pintype "bidirectional"))
    )
    (net (code "38") (name "Net-(U6-IO6)") (class "Default")
      (node (ref "TP38") (pin "1") (pinfunction "1_1") (pintype "passive"))
      (node (ref "U6") (pin "11") (pinfunction "IO6_11") (pintype "bidirectional"))
    )
    (net (code "39") (name "Net-(U6-IO7)") (class "Default")
      (node (ref "R71") (pin "2") (pinfunction "2_2") (pintype "passive"))
      (node (ref "TP39") (pin "1") (pinfunction "1_1") (pintype "passive"))
      (node (ref "U6") (pin "12") (pinfunction "IO7_12") (pintype "bidirectional"))
    )
    (net (code "40") (name "Net-(U6-~{RESET})") (class "Default")
      (node (ref "R56") (pin "1") (pinfunction "1_1") (pintype "passive"))
      (node (ref "U6") (pin "13") (pinfunction "~{RESET}_13") (pintype "input"))
    )
    (net (code "41") (name "Net-(U8-CIN1+)") (class "Default")
      (node (ref "R63") (pin "1") (pinfunction "1_1") (pintype "passive"))
      (node (ref "R64") (pin "2") (pinfunction "2_2") (pintype "passive"))
      (node (ref "TP25") (pin "1") (pinfunction "1_1") (pintype "passive"))
      (node (ref "U8") (pin "10") (pinfunction "CIN1+_10") (pintype "input"))
    )
    (net (code "42") (name "Net-(U8-CIN1-)") (class "Default")
      (node (ref "R61") (pin "1") (pinfunction "1_1") (pintype "passive"))
      (node (ref "R62") (pin "2") (pinfunction "2_2") (pintype "passive"))
      (node (ref "TP26") (pin "1") (pinfunction "1_1") (pintype "passive"))
      (node (ref "U8") (pin "11") (pinfunction "CIN1-_11") (pintype "input"))
    )
    (net (code "43") (name "Net-(U8-CIN2+)") (class "Default")
      (node (ref "R63") (pin "2") (pinfunction "2_2") (pintype "passive"))
      (node (ref "U8") (pin "12") (pinfunction "REF_12") (pintype "output"))
      (node (ref "U8") (pin "8") (pinfunction "CIN2+_8") (pintype "input"))
    )
    (net (code "44") (name "Net-(U8-INHIBIT)") (class "Default")
      (node (ref "R67") (pin "1") (pinfunction "1_1") (pintype "passive"))
      (node (ref "U8") (pin "5") (pinfunction "INHIBIT_5") (pintype "input"))
    )
    (net (code "45") (name "Net-(U8-IOUT)") (class "Default")
      (node (ref "R61") (pin "2") (pinfunction "2_2") (pintype "passive"))
      (node (ref "U8") (pin "14") (pinfunction "IOUT_14") (pintype "output"))
    )
    (net (code "46") (name "Net-(U8-POUT)") (class "Default")
      (node (ref "TP24") (pin "1") (pinfunction "1_1") (pintype "passive"))
      (node (ref "U8") (pin "13") (pinfunction "POUT_13") (pintype "output"))
    )
    (net (code "47") (name "Net-(U8-RS+)") (class "Default")
      (node (ref "Q2") (pin "1") (pinfunction "D_1") (pintype "passive"))
      (node (ref "Q2") (pin "2") (pinfunction "D_2") (pintype "passive"))
      (node (ref "Q2") (pin "5") (pinfunction "D_5") (pintype "passive"))
      (node (ref "Q2") (pin "6") (pinfunction "D_6") (pintype "passive"))
      (node (ref "R59") (pin "1") (pinfunction "1_1") (pintype "passive"))
      (node (ref "U8") (pin "16") (pinfunction "RS+_16") (pintype "passive"))
    )
    (net (code "48") (name "Net-(U9-PG)") (class "Default")
      (node (ref "TP31") (pin "1") (pinfunction "1_1") (pintype "passive"))
      (node (ref "U9") (pin "13") (pinfunction "PG_13") (pintype "open_collector"))
    )
    (net (code "49") (name "Net-(U9-SYNC)") (class "Default")
      (node (ref "R69") (pin "1") (pinfunction "1_1") (pintype "passive"))
      (node (ref "R70") (pin "2") (pinfunction "2_2") (pintype "passive"))
      (node (ref "TP32") (pin "1") (pinfunction "1_1") (pintype "passive"))
      (node (ref "U9") (pin "5") (pinfunction "SYNC_5") (pintype "input"))
    )
    (net (code "50") (name "ON{slash}~{OFF}") (class "Default")
      (node (ref "Q7") (pin "1") (pinfunction "G_1") (pintype "passive"))
      (node (ref "R58") (pin "2") (pinfunction "2_2") (pintype "passive"))
      (node (ref "TP27") (pin "1") (pinfunction "1_1") (pintype "passive"))
      (node (ref "U6") (pin "4") (pinfunction "IO0_4") (pintype "bidirectional"))
    )
    (net (code "51") (name "OPD_PWR") (class "Default")
      (node (ref "CF1") (pin "12") (pinfunction "12_12") (pintype "passive"))
      (node (ref "J7") (pin "19") (pinfunction "19_19") (pintype "passive"))
      (node (ref "J7") (pin "20") (pinfunction "20_20") (pintype "passive"))
      (node (ref "R41") (pin "1") (pinfunction "1_1") (pintype "passive"))
    )
    (net (code "52") (name "OPD_SCL") (class "Default")
      (node (ref "CF1") (pin "9") (pinfunction "9_9") (pintype "passive"))
      (node (ref "J7") (pin "17") (pinfunction "17_17") (pintype "passive"))
      (node (ref "J7") (pin "18") (pinfunction "18_18") (pintype "passive"))
      (node (ref "R54") (pin "1") (pinfunction "1_1") (pintype "passive"))
    )
    (net (code "53") (name "OPD_SDA") (class "Default")
      (node (ref "CF1") (pin "11") (pinfunction "11_11") (pintype "passive"))
      (node (ref "J7") (pin "15") (pinfunction "15_15") (pintype "passive"))
      (node (ref "J7") (pin "16") (pinfunction "16_16") (pintype "passive"))
      (node (ref "R55") (pin "1") (pinfunction "1_1") (pintype "passive"))
    )
    (net (code "54") (name "PA0") (class "Default")
      (node (ref "R9") (pin "2") (pinfunction "2_2") (pintype "passive"))
      (node (ref "U4") (pin "6") (pinfunction "PA0_6") (pintype "bidirectional"))
    )
    (net (code "55") (name "PA1") (class "Default")
      (node (ref "U4") (pin "7") (pinfunction "PA1_7") (pintype "bidirectional"))
    )
    (net (code "56") (name "PA2{slash}USART2_TX") (class "Default")
      (node (ref "U4") (pin "8") (pinfunction "PA2_8") (pintype "bidirectional"))
    )
    (net (code "57") (name "PA3{slash}USART2_RX") (class "Default")
      (node (ref "U4") (pin "9") (pinfunction "PA3_9") (pintype "bidirectional"))
    )
    (net (code "58") (name "PA4") (class "Default")
      (node (ref "U4") (pin "10") (pinfunction "PA4_10") (pintype "bidirectional"))
    )
    (net (code "59") (name "PA5{slash}SPI1_SCK") (class "Default")
      (node (ref "U4") (pin "11") (pinfunction "PA5_11") (pintype "bidirectional"))
    )
    (net (code "60") (name "PA6{slash}SPI1_MISO") (class "Default")
      (node (ref "U4") (pin "12") (pinfunction "PA6_12") (pintype "bidirectional"))
    )
    (net (code "61") (name "PA7{slash}SPI1_MOSI") (class "Default")
      (node (ref "U4") (pin "13") (pinfunction "PA7_13") (pintype "bidirectional"))
    )
    (net (code "62") (name "PA8") (class "Default")
      (node (ref "U4") (pin "18") (pinfunction "PA8_18") (pintype "bidirectional"))
    )
    (net (code "63") (name "PA15") (class "Default")
      (node (ref "U4") (pin "25") (pinfunction "PA15_25") (pintype "bidirectional"))
    )
    (net (code "64") (name "PB0") (class "Default")
      (node (ref "U4") (pin "14") (pinfunction "PB0_14") (pintype "bidirectional"))
    )
    (net (code "65") (name "PB1") (class "Default")
      (node (ref "U4") (pin "15") (pinfunction "PB1_15") (pintype "bidirectional"))
    )
    (net (code "66") (name "PB3") (class "Default")
      (node (ref "U4") (pin "26") (pinfunction "PB3_26") (pintype "bidirectional"))
    )
    (net (code "67") (name "PB4{slash}I2C-~{RESET}") (class "Default")
      (node (ref "CF2") (pin "10") (pinfunction "10_10") (pintype "passive"))
      (node (ref "CF2") (pin "9") (pinfunction "9_9") (pintype "passive"))
      (node (ref "U4") (pin "27") (pinfunction "PB4_27") (pintype "bidirectional"))
    )
    (net (code "68") (name "PB5{slash}I2C-~{INT}") (class "Default")
      (node (ref "CF2") (pin "7") (pinfunction "7_7") (pintype "passive"))
      (node (ref "CF2") (pin "8") (pinfunction "8_8") (pintype "passive"))
      (node (ref "R11") (pin "1") (pinfunction "1_1") (pintype "passive"))
      (node (ref "U4") (pin "28") (pinfunction "PB5_28") (pintype "bidirectional"))
    )
    (net (code "69") (name "PB6{slash}SCL") (class "Default")
      (node (ref "CF2") (pin "5") (pinfunction "5_5") (pintype "passive"))
      (node (ref "CF2") (pin "6") (pinfunction "6_6") (pintype "passive"))
      (node (ref "R7") (pin "1") (pinfunction "1_1") (pintype "passive"))
      (node (ref "U4") (pin "29") (pinfunction "PB6_29") (pintype "bidirectional"))
    )
    (net (code "70") (name "PB7{slash}SDA") (class "Default")
      (node (ref "CF2") (pin "3") (pinfunction "3_3") (pintype "passive"))
      (node (ref "CF2") (pin "4") (pinfunction "4_4") (pintype "passive"))
      (node (ref "R10") (pin "1") (pinfunction "1_1") (pintype "passive"))
      (node (ref "U4") (pin "30") (pinfunction "PB7_30") (pintype "bidirectional"))
    )
    (net (code "71") (name "PEN-SCL-FILT") (class "Default")
      (node (ref "R43") (pin "1") (pinfunction "1_1") (pintype "passive"))
      (node (ref "R47") (pin "1") (pinfunction "1_1") (pintype "passive"))
      (node (ref "R51") (pin "1") (pinfunction "1_1") (pintype "passive"))
      (node (ref "R54") (pin "2") (pinfunction "2_2") (pintype "passive"))
      (node (ref "TP40") (pin "1") (pinfunction "1_1") (pintype "passive"))
      (node (ref "U6") (pin "15") (pinfunction "SCL_15") (pintype "input"))
    )
    (net (code "72") (name "PEN-SDA-FILT") (class "Default")
      (node (ref "R45") (pin "2") (pinfunction "2_2") (pintype "passive"))
      (node (ref "R49") (pin "2") (pinfunction "2_2") (pintype "passive"))
      (node (ref "R53") (pin "2") (pinfunction "2_2") (pintype "passive"))
      (node (ref "R55") (pin "2") (pinfunction "2_2") (pintype "passive"))
      (node (ref "TP41") (pin "1") (pinfunction "1_1") (pintype "passive"))
      (node (ref "U6") (pin "16") (pinfunction "SDA_16") (pintype "bidirectional"))
    )
    (net (code "73") (name "SPARE1") (class "Default")
      (node (ref "J7") (pin "11") (pinfunction "11_11") (pintype "passive"))
      (node (ref "J7") (pin "12") (pinfunction "12_12") (pintype "passive"))
    )
    (net (code "74") (name "SPARE2") (class "Default")
      (node (ref "J7") (pin "10") (pinfunction "10_10") (pintype "passive"))
      (node (ref "J7") (pin "9") (pinfunction "9_9") (pintype "passive"))
    )
    (net (code "75") (name "SPARE3") (class "Default")
      (node (ref "J7") (pin "7") (pinfunction "7_7") (pintype "passive"))
      (node (ref "J7") (pin "8") (pinfunction "8_8") (pintype "passive"))
    )
    (net (code "76") (name "SPARE4") (class "Default")
      (node (ref "J7") (pin "5") (pinfunction "5_5") (pintype "passive"))
      (node (ref "J7") (pin "6") (pinfunction "6_6") (pintype "passive"))
    )
    (net (code "77") (name "SPARE5") (class "Default")
      (node (ref "J7") (pin "3") (pinfunction "3_3") (pintype "passive"))
      (node (ref "J7") (pin "4") (pinfunction "4_4") (pintype "passive"))
    )
    (net (code "78") (name "SPARE6") (class "Default")
      (node (ref "J7") (pin "1") (pinfunction "1_1") (pintype "passive"))
      (node (ref "J7") (pin "2") (pinfunction "2_2") (pintype "passive"))
    )
    (net (code "79") (name "SWCLK") (class "Default")
      (node (ref "J8") (pin "4") (pinfunction "SWDCLK/TCK_4") (pintype "passive"))
      (node (ref "U4") (pin "24") (pinfunction "PA14-SWCLK_24") (pintype "bidirectional"))
    )
    (net (code "80") (name "SWDIO") (class "Default")
      (node (ref "J8") (pin "2") (pinfunction "SWDIO/TMS_2") (pintype "passive"))
      (node (ref "U4") (pin "23") (pinfunction "PA13-SWDIO_23") (pintype "bidirectional"))
    )
    (net (code "81") (name "VBUS") (class "Default")
      (node (ref "CF1") (pin "5") (pinfunction "5_5") (pintype "passive"))
      (node (ref "CF1") (pin "6") (pinfunction "6_6") (pintype "passive"))
      (node (ref "J3") (pin "5") (pinfunction "5_5") (pintype "passive"))
      (node (ref "J3") (pin "6") (pinfunction "6_6") (pintype "passive"))
      (node (ref "J4") (pin "5") (pinfunction "5_5") (pintype "passive"))
      (node (ref "J4") (pin "6") (pinfunction "6_6") (pintype "passive"))
      (node (ref "J5") (pin "5") (pinfunction "5_5") (pintype "passive"))
      (node (ref "J5") (pin "6") (pinfunction "6_6") (pintype "passive"))
      (node (ref "J6") (pin "5") (pinfunction "5_5") (pintype "passive"))
      (node (ref "J6") (pin "6") (pinfunction "6_6") (pintype "passive"))
      (node (ref "J7") (pin "25") (pinfunction "25_25") (pintype "passive"))
      (node (ref "J7") (pin "26") (pinfunction "26_26") (pintype "passive"))
      (node (ref "J7") (pin "27") (pinfunction "27_27") (pintype "passive"))
      (node (ref "J7") (pin "28") (pinfunction "28_28") (pintype "passive"))
      (node (ref "Q2") (pin "4") (pinfunction "S_4") (pintype "passive"))
      (node (ref "R57") (pin "2") (pinfunction "2_2") (pintype "passive"))
    )
    (net (code "82") (name "VBUSP") (class "Default")
      (node (ref "C11") (pin "1") (pinfunction "1_1") (pintype "passive"))
      (node (ref "C16") (pin "1") (pinfunction "1_1") (pintype "passive"))
      (node (ref "C9") (pin "2") (pinfunction "2_2") (pintype "passive"))
      (node (ref "Q1") (pin "1") (pinfunction "D_1") (pintype "passive"))
      (node (ref "Q1") (pin "2") (pinfunction "D_2") (pintype "passive"))
      (node (ref "Q1") (pin "5") (pinfunction "D_5") (pintype "passive"))
      (node (ref "Q1") (pin "6") (pinfunction "D_6") (pintype "passive"))
      (node (ref "R39") (pin "2") (pinfunction "2_2") (pintype "passive"))
      (node (ref "R69") (pin "2") (pinfunction "2_2") (pintype "passive"))
      (node (ref "TP30") (pin "1") (pinfunction "1_1") (pintype "passive"))
      (node (ref "U9") (pin "2") (pinfunction "VIN_2") (pintype "power_in"))
      (node (ref "U9") (pin "3") (pinfunction "VIN_3") (pintype "power_in"))
      (node (ref "U9") (pin "4") (pinfunction "EN_4") (pintype "input"))
      (node (ref "U9") (pin "8") (pinfunction "VIN_8") (pintype "power_in"))
    )
    (net (code "83") (name "VPD") (class "Default")
      (node (ref "C6") (pin "2") (pinfunction "2_2") (pintype "passive"))
      (node (ref "R41") (pin "2") (pinfunction "2_2") (pintype "passive"))
      (node (ref "R42") (pin "2") (pinfunction "2_2") (pintype "passive"))
      (node (ref "R46") (pin "2") (pinfunction "2_2") (pintype "passive"))
      (node (ref "R50") (pin "2") (pinfunction "2_2") (pintype "passive"))
      (node (ref "R56") (pin "2") (pinfunction "2_2") (pintype "passive"))
      (node (ref "R68") (pin "2") (pinfunction "2_2") (pintype "passive"))
      (node (ref "TP34") (pin "1") (pinfunction "1_1") (pintype "passive"))
      (node (ref "U6") (pin "14") (pinfunction "V+_14") (pintype "power_in"))
    )
    (net (code "84") (name "unconnected-(J8-NC{slash}TDI-Pad8)") (class "Default")
      (node (ref "J8") (pin "8") (pinfunction "NC/TDI_8") (pintype "passive"))
    )
    (net (code "85") (name "unconnected-(J8-SWO{slash}TDO-Pad6)") (class "Default")
      (node (ref "J8") (pin "6") (pinfunction "SWO/TDO_6") (pintype "passive"))
    )
    (net (code "86") (name "~{FAULT}") (class "Default")
      (node (ref "Q8") (pin "3") (pinfunction "D_3") (pintype "passive"))
      (node (ref "R68") (pin "1") (pinfunction "1_1") (pintype "passive"))
      (node (ref "TP29") (pin "1") (pinfunction "1_1") (pintype "passive"))
      (node (ref "U6") (pin "7") (pinfunction "IO2_7") (pintype "bidirectional"))
    )
    (net (code "87") (name "~{SHUTDOWN}") (class "Default")
      (node (ref "CF1") (pin "10") (pinfunction "10_10") (pintype "passive"))
      (node (ref "J3") (pin "1") (pinfunction "1_1") (pintype "passive"))
      (node (ref "J3") (pin "2") (pinfunction "2_2") (pintype "passive"))
      (node (ref "J4") (pin "1") (pinfunction "1_1") (pintype "passive"))
      (node (ref "J4") (pin "2") (pinfunction "2_2") (pintype "passive"))
      (node (ref "J5") (pin "1") (pinfunction "1_1") (pintype "passive"))
      (node (ref "J5") (pin "2") (pinfunction "2_2") (pintype "passive"))
      (node (ref "J6") (pin "1") (pinfunction "1_1") (pintype "passive"))
      (node (ref "J6") (pin "2") (pinfunction "2_2") (pintype "passive"))
      (node (ref "J7") (pin "39") (pinfunction "39_39") (pintype "passive"))
      (node (ref "J7") (pin "40") (pinfunction "40_40") (pintype "passive"))
    )
  )
)
